# HeaterMeterPI.net
KiCad netlist of a schematic drawn in EAGLE
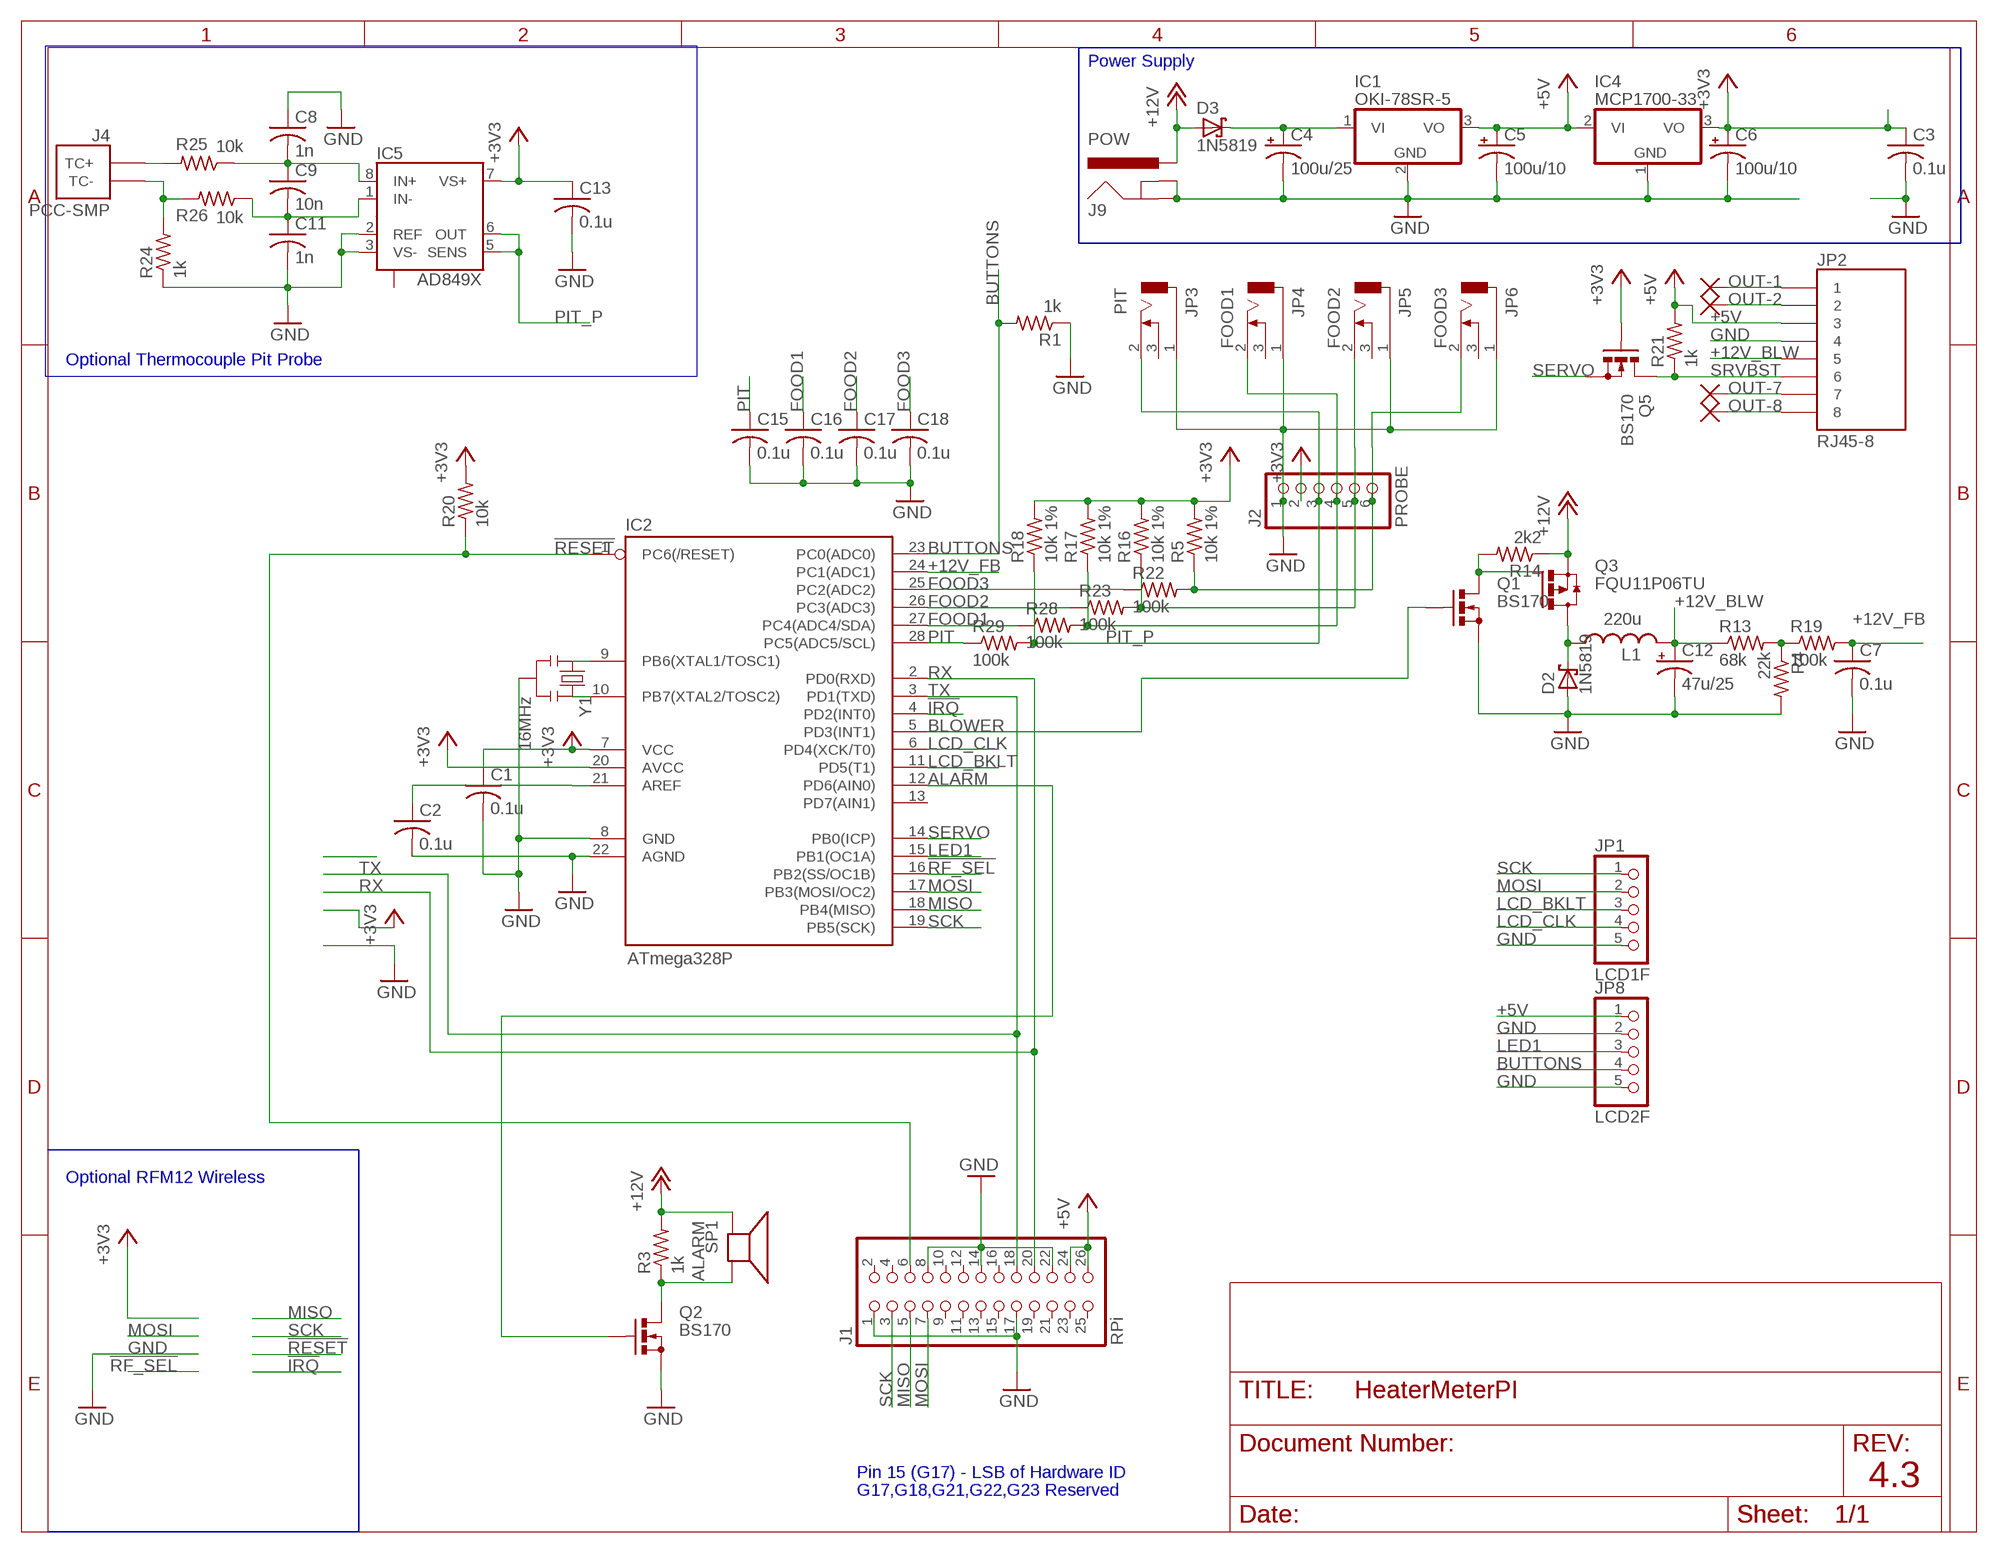
[diagram p0: schematic, sheet 1]

(export (version "E")
  (design (tool "Eeschema 10.0.6"))
  (components
    (comp (ref "C1")
      (value "0.1u")
      (footprint "eagle-import:C025-025X050")
      (libsource (lib "eagle-import") (part "C-US025-025X050"))
    )
    (comp (ref "C2")
      (value "0.1u")
      (footprint "eagle-import:C025-025X050")
      (libsource (lib "eagle-import") (part "C-US025-025X050"))
    )
    (comp (ref "C3")
      (value "0.1u")
      (footprint "eagle-import:C025-025X050")
      (libsource (lib "eagle-import") (part "C-US025-025X050"))
    )
    (comp (ref "C4")
      (value "100u/25")
      (footprint "eagle-import:E2,5-6")
      (libsource (lib "eagle-import") (part "CPOL-USE2.5-6"))
    )
    (comp (ref "C5")
      (value "100u/10")
      (footprint "eagle-import:E2,5-5")
      (libsource (lib "eagle-import") (part "CPOL-USE2.5-5"))
    )
    (comp (ref "C6")
      (value "100u/10")
      (footprint "eagle-import:E2,5-5")
      (libsource (lib "eagle-import") (part "CPOL-USE2.5-5"))
    )
    (comp (ref "C7")
      (value "0.1u")
      (footprint "eagle-import:C025-025X050")
      (libsource (lib "eagle-import") (part "C-US025-025X050"))
    )
    (comp (ref "C8")
      (value "1n")
      (footprint "eagle-import:C0805")
      (libsource (lib "eagle-import") (part "C-USC0805"))
    )
    (comp (ref "C9")
      (value "10n")
      (footprint "eagle-import:C0805")
      (libsource (lib "eagle-import") (part "C-USC0805"))
    )
    (comp (ref "C11")
      (value "1n")
      (footprint "eagle-import:C0805")
      (libsource (lib "eagle-import") (part "C-USC0805"))
    )
    (comp (ref "C12")
      (value "47u/25")
      (footprint "eagle-import:E2,5-5")
      (libsource (lib "eagle-import") (part "CPOL-USE2.5-5"))
    )
    (comp (ref "C13")
      (value "0.1u")
      (footprint "eagle-import:C0805")
      (libsource (lib "eagle-import") (part "C-USC0805"))
    )
    (comp (ref "C15")
      (value "0.1u")
      (footprint "eagle-import:C025-025X050")
      (libsource (lib "eagle-import") (part "C-US025-025X050"))
    )
    (comp (ref "C16")
      (value "0.1u")
      (footprint "eagle-import:C025-025X050")
      (libsource (lib "eagle-import") (part "C-US025-025X050"))
    )
    (comp (ref "C17")
      (value "0.1u")
      (footprint "eagle-import:C025-025X050")
      (libsource (lib "eagle-import") (part "C-US025-025X050"))
    )
    (comp (ref "C18")
      (value "0.1u")
      (footprint "eagle-import:C025-025X050")
      (libsource (lib "eagle-import") (part "C-US025-025X050"))
    )
    (comp (ref "D2")
      (value "1N5819")
      (footprint "eagle-import:DO41-7")
      (libsource (lib "eagle-import") (part "1N5819"))
    )
    (comp (ref "D3")
      (value "1N5819")
      (footprint "eagle-import:DO41-7")
      (libsource (lib "eagle-import") (part "1N5819"))
    )
    (comp (ref "IC1")
      (value "OKI-78SR-5")
      (footprint "eagle-import:TO220HMURATA")
      (libsource (lib "eagle-import") (part "OKI-78SR-H05"))
    )
    (comp (ref "IC2")
      (value "ATmega328P")
      (footprint "eagle-import:DIL28-3")
      (libsource (lib "eagle-import") (part "AVR-MEGA8-PPTH"))
    )
    (comp (ref "IC4")
      (value "MCP1700-33")
      (footprint "eagle-import:TO92")
      (libsource (lib "eagle-import") (part "MCP1700-33"))
    )
    (comp (ref "IC5")
      (value "AD849X")
      (footprint "eagle-import:MSOP8")
      (libsource (lib "eagle-import") (part "AD849X"))
    )
    (comp (ref "J1")
      (value "RPi")
      (footprint "eagle-import:2X13")
      (libsource (lib "eagle-import") (part "PINHD-2X13"))
    )
    (comp (ref "J2")
      (value "PROBE")
      (footprint "eagle-import:1X06")
      (libsource (lib "eagle-import") (part "PINHD-1X6"))
    )
    (comp (ref "J4")
      (value "PCC-SMP")
      (footprint "eagle-import:PCC-SMP")
      (libsource (lib "eagle-import") (part "THERMOCOUPLE"))
    )
    (comp (ref "J9")
      (value "POW")
      (footprint "eagle-import:BARREL-2.1")
      (libsource (lib "eagle-import") (part "POWERJACKPTH"))
    )
    (comp (ref "JP1")
      (value "LCD1F")
      (footprint "eagle-import:1X05")
      (libsource (lib "eagle-import") (part "PINHD-1X5"))
    )
    (comp (ref "JP2")
      (value "RJ45-8")
      (footprint "eagle-import:RJ45-8-1H")
      (libsource (lib "eagle-import") (part "RJ45-8"))
    )
    (comp (ref "JP3")
      (value "PIT")
      (footprint "eagle-import:CUI-MJ-2508")
      (libsource (lib "eagle-import") (part "AUDIO-MONOCUI"))
    )
    (comp (ref "JP4")
      (value "FOOD1")
      (footprint "eagle-import:CUI-MJ-2508")
      (libsource (lib "eagle-import") (part "AUDIO-MONOCUI"))
    )
    (comp (ref "JP5")
      (value "FOOD2")
      (footprint "eagle-import:CUI-MJ-2508")
      (libsource (lib "eagle-import") (part "AUDIO-MONOCUI"))
    )
    (comp (ref "JP6")
      (value "FOOD3")
      (footprint "eagle-import:CUI-MJ-2508")
      (libsource (lib "eagle-import") (part "AUDIO-MONOCUI"))
    )
    (comp (ref "JP8")
      (value "LCD2F")
      (footprint "eagle-import:1X05")
      (libsource (lib "eagle-import") (part "PINHD-1X5"))
    )
    (comp (ref "L1")
      (value "220u")
      (footprint "eagle-import:E5-9")
      (libsource (lib "eagle-import") (part "INDUCTOR9MM"))
    )
    (comp (ref "Q1")
      (value "BS170")
      (footprint "eagle-import:SOT54E")
      (libsource (lib "eagle-import") (part "BS170"))
    )
    (comp (ref "Q2")
      (value "BS170")
      (footprint "eagle-import:SOT54E")
      (libsource (lib "eagle-import") (part "BS170"))
    )
    (comp (ref "Q3")
      (value "FQU11P06TU")
      (footprint "eagle-import:TO251")
      (libsource (lib "eagle-import") (part "MOSFET-P"))
    )
    (comp (ref "Q5")
      (value "BS170")
      (footprint "eagle-import:SOT54E")
      (libsource (lib "eagle-import") (part "BS170"))
    )
    (comp (ref "R1")
      (value "1k")
      (footprint "eagle-import:0204_7")
      (libsource (lib "eagle-import") (part "R-US_0204/7"))
    )
    (comp (ref "R3")
      (value "1k")
      (footprint "eagle-import:0204_7")
      (libsource (lib "eagle-import") (part "R-US_0204/7"))
    )
    (comp (ref "R4")
      (value "22k")
      (footprint "eagle-import:0204_7")
      (libsource (lib "eagle-import") (part "R-US_0204/7"))
    )
    (comp (ref "R5")
      (value "10k 1%")
      (footprint "eagle-import:0207_2V")
      (libsource (lib "eagle-import") (part "R-US_0207/2V"))
    )
    (comp (ref "R13")
      (value "68k")
      (footprint "eagle-import:0204_7")
      (libsource (lib "eagle-import") (part "R-US_0204/7"))
    )
    (comp (ref "R14")
      (value "2k2")
      (footprint "eagle-import:0204_7")
      (libsource (lib "eagle-import") (part "R-US_0204/7"))
    )
    (comp (ref "R16")
      (value "10k 1%")
      (footprint "eagle-import:0207_2V")
      (libsource (lib "eagle-import") (part "R-US_0207/2V"))
    )
    (comp (ref "R17")
      (value "10k 1%")
      (footprint "eagle-import:0207_2V")
      (libsource (lib "eagle-import") (part "R-US_0207/2V"))
    )
    (comp (ref "R18")
      (value "10k 1%")
      (footprint "eagle-import:0207_2V")
      (libsource (lib "eagle-import") (part "R-US_0207/2V"))
    )
    (comp (ref "R19")
      (value "100k")
      (footprint "eagle-import:0204_7")
      (libsource (lib "eagle-import") (part "R-US_0204/7"))
    )
    (comp (ref "R20")
      (value "10k")
      (footprint "eagle-import:0204_7")
      (libsource (lib "eagle-import") (part "R-US_0204/7"))
    )
    (comp (ref "R21")
      (value "1k")
      (footprint "eagle-import:0204_7")
      (libsource (lib "eagle-import") (part "R-US_0204/7"))
    )
    (comp (ref "R22")
      (value "100k")
      (footprint "eagle-import:0207_2V")
      (libsource (lib "eagle-import") (part "R-US_0207/2V"))
    )
    (comp (ref "R23")
      (value "100k")
      (footprint "eagle-import:0207_2V")
      (libsource (lib "eagle-import") (part "R-US_0207/2V"))
    )
    (comp (ref "R24")
      (value "1k")
      (footprint "eagle-import:R0805")
      (libsource (lib "eagle-import") (part "R-US_R0805"))
    )
    (comp (ref "R25")
      (value "10k")
      (footprint "eagle-import:R0805")
      (libsource (lib "eagle-import") (part "R-US_R0805"))
    )
    (comp (ref "R26")
      (value "10k")
      (footprint "eagle-import:R0805")
      (libsource (lib "eagle-import") (part "R-US_R0805"))
    )
    (comp (ref "R28")
      (value "100k")
      (footprint "eagle-import:0207_2V")
      (libsource (lib "eagle-import") (part "R-US_0207/2V"))
    )
    (comp (ref "R29")
      (value "100k")
      (footprint "eagle-import:0207_2V")
      (libsource (lib "eagle-import") (part "R-US_0207/2V"))
    )
    (comp (ref "SP1")
      (value "ALARM")
      (footprint "eagle-import:AL11P")
      (libsource (lib "eagle-import") (part "SPEAKER/AL11P"))
    )
    (comp (ref "U$1")
      (value "THROUGH-HOLE")
      (footprint "eagle-import:PAD-032")
      (libsource (lib "eagle-import") (part "THROUGH-HOLE"))
    )
    (comp (ref "U$2")
      (value "THROUGH-HOLE")
      (footprint "eagle-import:PAD-032")
      (libsource (lib "eagle-import") (part "THROUGH-HOLE"))
    )
    (comp (ref "U$3")
      (value "THROUGH-HOLE")
      (footprint "eagle-import:PAD-032")
      (libsource (lib "eagle-import") (part "THROUGH-HOLE"))
    )
    (comp (ref "U$4")
      (value "THROUGH-HOLE")
      (footprint "eagle-import:PAD-032")
      (libsource (lib "eagle-import") (part "THROUGH-HOLE"))
    )
    (comp (ref "Y1")
      (value "16MHz")
      (footprint "eagle-import:RESONATOR-PTH")
      (libsource (lib "eagle-import") (part "RESONATORRESONATOR-PTH"))
    )
  )
  (nets
    (net (code "1") (name "+3V3") (class "Default")
      (node (ref "C1") (pin "1") (pinfunction "1_1") (pintype "passive"))
      (node (ref "C13") (pin "1") (pinfunction "1_1") (pintype "passive"))
      (node (ref "C3") (pin "1") (pinfunction "1_1") (pintype "passive"))
      (node (ref "C6") (pin "+") (pinfunction "+_+") (pintype "passive"))
      (node (ref "IC2") (pin "20") (pinfunction "AVCC_20") (pintype "bidirectional"))
      (node (ref "IC2") (pin "7") (pinfunction "VCC_7") (pintype "bidirectional"))
      (node (ref "IC4") (pin "3") (pinfunction "VO_3") (pintype "passive"))
      (node (ref "IC5") (pin "7") (pinfunction "VS+_7") (pintype "power_in"))
      (node (ref "J2") (pin "2") (pinfunction "2_2") (pintype "passive"))
      (node (ref "Q5") (pin "G") (pinfunction "G_G") (pintype "passive"))
      (node (ref "R16") (pin "2") (pinfunction "2_2") (pintype "passive"))
      (node (ref "R17") (pin "2") (pinfunction "2_2") (pintype "passive"))
      (node (ref "R18") (pin "2") (pinfunction "2_2") (pintype "passive"))
      (node (ref "R20") (pin "2") (pinfunction "2_2") (pintype "passive"))
      (node (ref "R5") (pin "2") (pinfunction "2_2") (pintype "passive"))
    )
    (net (code "2") (name "+5V") (class "Default")
      (node (ref "C5") (pin "+") (pinfunction "+_+") (pintype "passive"))
      (node (ref "IC1") (pin "3") (pinfunction "VO_3") (pintype "passive"))
      (node (ref "IC4") (pin "2") (pinfunction "VI_2") (pintype "input"))
      (node (ref "J1") (pin "24") (pinfunction "24_24") (pintype "passive"))
      (node (ref "J1") (pin "26") (pinfunction "26_26") (pintype "passive"))
      (node (ref "JP2") (pin "3") (pinfunction "3_3") (pintype "bidirectional"))
      (node (ref "JP8") (pin "1") (pinfunction "1_1") (pintype "passive"))
      (node (ref "R21") (pin "2") (pinfunction "2_2") (pintype "passive"))
    )
    (net (code "3") (name "+12V") (class "Default")
      (node (ref "D3") (pin "A") (pinfunction "A_A") (pintype "passive"))
      (node (ref "J9") (pin "PWR") (pinfunction "PWR_PWR") (pintype "bidirectional"))
      (node (ref "Q3") (pin "3") (pinfunction "S_3") (pintype "passive"))
      (node (ref "R14") (pin "1") (pinfunction "1_1") (pintype "passive"))
      (node (ref "R3") (pin "2") (pinfunction "2_2") (pintype "passive"))
      (node (ref "SP1") (pin "+") (pinfunction "+_+") (pintype "passive"))
    )
    (net (code "4") (name "/+12V_BLW") (class "Default")
      (node (ref "C12") (pin "+") (pinfunction "+_+") (pintype "passive"))
      (node (ref "JP2") (pin "5") (pinfunction "5_5") (pintype "bidirectional"))
      (node (ref "L1") (pin "NEG") (pinfunction "2_NEG") (pintype "passive"))
      (node (ref "R13") (pin "1") (pinfunction "1_1") (pintype "passive"))
    )
    (net (code "5") (name "/+12V_FB") (class "Default")
      (node (ref "C7") (pin "1") (pinfunction "1_1") (pintype "passive"))
      (node (ref "IC2") (pin "24") (pinfunction "PC1(ADC1)_24") (pintype "bidirectional"))
      (node (ref "R19") (pin "2") (pinfunction "2_2") (pintype "passive"))
    )
    (net (code "6") (name "/ALARM") (class "Default")
      (node (ref "IC2") (pin "12") (pinfunction "PD6(AIN0)_12") (pintype "bidirectional"))
      (node (ref "Q2") (pin "G") (pinfunction "G_G") (pintype "passive"))
    )
    (net (code "7") (name "/BLOWER") (class "Default")
      (node (ref "IC2") (pin "5") (pinfunction "PD3(INT1)_5") (pintype "bidirectional"))
      (node (ref "Q1") (pin "G") (pinfunction "G_G") (pintype "passive"))
    )
    (net (code "8") (name "/BUTTONS") (class "Default")
      (node (ref "IC2") (pin "23") (pinfunction "PC0(ADC0)_23") (pintype "bidirectional"))
      (node (ref "JP8") (pin "4") (pinfunction "4_4") (pintype "passive"))
      (node (ref "R1") (pin "2") (pinfunction "2_2") (pintype "passive"))
    )
    (net (code "9") (name "/FOOD1") (class "Default")
      (node (ref "C16") (pin "1") (pinfunction "1_1") (pintype "passive"))
      (node (ref "IC2") (pin "27") (pinfunction "PC4(ADC4/SDA)_27") (pintype "bidirectional"))
      (node (ref "R28") (pin "1") (pinfunction "1_1") (pintype "passive"))
    )
    (net (code "10") (name "/FOOD2") (class "Default")
      (node (ref "C17") (pin "1") (pinfunction "1_1") (pintype "passive"))
      (node (ref "IC2") (pin "26") (pinfunction "PC3(ADC3)_26") (pintype "bidirectional"))
      (node (ref "R23") (pin "1") (pinfunction "1_1") (pintype "passive"))
    )
    (net (code "11") (name "/FOOD3") (class "Default")
      (node (ref "C18") (pin "1") (pinfunction "1_1") (pintype "passive"))
      (node (ref "IC2") (pin "25") (pinfunction "PC2(ADC2)_25") (pintype "bidirectional"))
      (node (ref "R22") (pin "1") (pinfunction "1_1") (pintype "passive"))
    )
    (net (code "12") (name "/LCD_BKLT") (class "Default")
      (node (ref "IC2") (pin "11") (pinfunction "PD5(T1)_11") (pintype "bidirectional"))
      (node (ref "JP1") (pin "3") (pinfunction "3_3") (pintype "passive"))
    )
    (net (code "13") (name "/LCD_CLK") (class "Default")
      (node (ref "IC2") (pin "6") (pinfunction "PD4(XCK/T0)_6") (pintype "bidirectional"))
      (node (ref "JP1") (pin "4") (pinfunction "4_4") (pintype "passive"))
    )
    (net (code "14") (name "/LED1") (class "Default")
      (node (ref "IC2") (pin "15") (pinfunction "PB1(OC1A)_15") (pintype "bidirectional"))
      (node (ref "JP8") (pin "3") (pinfunction "3_3") (pintype "passive"))
    )
    (net (code "15") (name "/MISO") (class "Default")
      (node (ref "IC2") (pin "18") (pinfunction "PB4(MISO)_18") (pintype "bidirectional"))
      (node (ref "J1") (pin "5") (pinfunction "5_5") (pintype "passive"))
    )
    (net (code "16") (name "/MOSI") (class "Default")
      (node (ref "IC2") (pin "17") (pinfunction "PB3(MOSI/OC2)_17") (pintype "bidirectional"))
      (node (ref "J1") (pin "7") (pinfunction "7_7") (pintype "passive"))
      (node (ref "JP1") (pin "2") (pinfunction "2_2") (pintype "passive"))
    )
    (net (code "17") (name "/OUT-1") (class "Default")
      (node (ref "JP2") (pin "1") (pinfunction "1_1") (pintype "bidirectional"))
      (node (ref "U$3") (pin "P") (pinfunction "P_P") (pintype "output"))
    )
    (net (code "18") (name "/OUT-2") (class "Default")
      (node (ref "JP2") (pin "2") (pinfunction "2_2") (pintype "bidirectional"))
      (node (ref "U$4") (pin "P") (pinfunction "P_P") (pintype "output"))
    )
    (net (code "19") (name "/OUT-7") (class "Default")
      (node (ref "JP2") (pin "7") (pinfunction "7_7") (pintype "bidirectional"))
      (node (ref "U$2") (pin "P") (pinfunction "P_P") (pintype "output"))
    )
    (net (code "20") (name "/OUT-8") (class "Default")
      (node (ref "JP2") (pin "8") (pinfunction "8_8") (pintype "bidirectional"))
      (node (ref "U$1") (pin "P") (pinfunction "P_P") (pintype "output"))
    )
    (net (code "21") (name "/PIT") (class "Default")
      (node (ref "C15") (pin "1") (pinfunction "1_1") (pintype "passive"))
      (node (ref "IC2") (pin "28") (pinfunction "PC5(ADC5/SCL)_28") (pintype "bidirectional"))
      (node (ref "R29") (pin "1") (pinfunction "1_1") (pintype "passive"))
    )
    (net (code "22") (name "/PIT_P") (class "Default")
      (node (ref "IC5") (pin "5") (pinfunction "SENS_5") (pintype "bidirectional"))
      (node (ref "IC5") (pin "6") (pinfunction "OUT_6") (pintype "output"))
      (node (ref "J2") (pin "3") (pinfunction "3_3") (pintype "passive"))
      (node (ref "JP3") (pin "2") (pinfunction "2_2") (pintype "passive"))
      (node (ref "R18") (pin "1") (pinfunction "1_1") (pintype "passive"))
      (node (ref "R29") (pin "2") (pinfunction "2_2") (pintype "passive"))
    )
    (net (code "23") (name "/RX") (class "Default")
      (node (ref "IC2") (pin "2") (pinfunction "PD0(RXD)_2") (pintype "bidirectional"))
      (node (ref "J1") (pin "20") (pinfunction "20_20") (pintype "passive"))
    )
    (net (code "24") (name "/SCK") (class "Default")
      (node (ref "IC2") (pin "19") (pinfunction "PB5(SCK)_19") (pintype "bidirectional"))
      (node (ref "J1") (pin "3") (pinfunction "3_3") (pintype "passive"))
      (node (ref "JP1") (pin "1") (pinfunction "1_1") (pintype "passive"))
    )
    (net (code "25") (name "/SERVO") (class "Default")
      (node (ref "IC2") (pin "14") (pinfunction "PB0(ICP)_14") (pintype "bidirectional"))
      (node (ref "Q5") (pin "S") (pinfunction "S_S") (pintype "passive"))
    )
    (net (code "26") (name "/SRVBST") (class "Default")
      (node (ref "JP2") (pin "6") (pinfunction "6_6") (pintype "bidirectional"))
      (node (ref "Q5") (pin "D") (pinfunction "D_D") (pintype "passive"))
      (node (ref "R21") (pin "1") (pinfunction "1_1") (pintype "passive"))
    )
    (net (code "27") (name "/TX") (class "Default")
      (node (ref "IC2") (pin "3") (pinfunction "PD1(TXD)_3") (pintype "bidirectional"))
      (node (ref "J1") (pin "18") (pinfunction "18_18") (pintype "passive"))
    )
    (net (code "28") (name "/~{IRQ}") (class "Default")
      (node (ref "IC2") (pin "4") (pinfunction "PD2(INT0)_4") (pintype "bidirectional"))
    )
    (net (code "29") (name "/~{RESET}") (class "Default")
      (node (ref "IC2") (pin "1") (pinfunction "PC6(/RESET)_1") (pintype "bidirectional"))
      (node (ref "J1") (pin "6") (pinfunction "6_6") (pintype "passive"))
      (node (ref "R20") (pin "1") (pinfunction "1_1") (pintype "passive"))
    )
    (net (code "30") (name "/~{RF_SEL}") (class "Default")
      (node (ref "IC2") (pin "16") (pinfunction "PB2(SS/OC1B)_16") (pintype "bidirectional"))
    )
    (net (code "31") (name "GND") (class "Default")
      (node (ref "C1") (pin "2") (pinfunction "2_2") (pintype "passive"))
      (node (ref "C11") (pin "2") (pinfunction "2_2") (pintype "passive"))
      (node (ref "C12") (pin "-") (pinfunction "-_-") (pintype "passive"))
      (node (ref "C13") (pin "2") (pinfunction "2_2") (pintype "passive"))
      (node (ref "C15") (pin "2") (pinfunction "2_2") (pintype "passive"))
      (node (ref "C16") (pin "2") (pinfunction "2_2") (pintype "passive"))
      (node (ref "C17") (pin "2") (pinfunction "2_2") (pintype "passive"))
      (node (ref "C18") (pin "2") (pinfunction "2_2") (pintype "passive"))
      (node (ref "C2") (pin "2") (pinfunction "2_2") (pintype "passive"))
      (node (ref "C3") (pin "2") (pinfunction "2_2") (pintype "passive"))
      (node (ref "C4") (pin "-") (pinfunction "-_-") (pintype "passive"))
      (node (ref "C5") (pin "-") (pinfunction "-_-") (pintype "passive"))
      (node (ref "C6") (pin "-") (pinfunction "-_-") (pintype "passive"))
      (node (ref "C7") (pin "2") (pinfunction "2_2") (pintype "passive"))
      (node (ref "C8") (pin "1") (pinfunction "1_1") (pintype "passive"))
      (node (ref "D2") (pin "A") (pinfunction "A_A") (pintype "passive"))
      (node (ref "IC1") (pin "2") (pinfunction "GND_2") (pintype "passive"))
      (node (ref "IC2") (pin "22") (pinfunction "AGND_22") (pintype "bidirectional"))
      (node (ref "IC2") (pin "8") (pinfunction "GND_8") (pintype "bidirectional"))
      (node (ref "IC4") (pin "1") (pinfunction "GND_1") (pintype "passive"))
      (node (ref "IC5") (pin "2") (pinfunction "REF_2") (pintype "input"))
      (node (ref "IC5") (pin "3") (pinfunction "VS-_3") (pintype "power_in"))
      (node (ref "J1") (pin "1") (pinfunction "1_1") (pintype "passive"))
      (node (ref "J1") (pin "14") (pinfunction "14_14") (pintype "passive"))
      (node (ref "J1") (pin "17") (pinfunction "17_17") (pintype "passive"))
      (node (ref "J1") (pin "22") (pinfunction "22_22") (pintype "passive"))
      (node (ref "J1") (pin "8") (pinfunction "8_8") (pintype "passive"))
      (node (ref "J2") (pin "1") (pinfunction "1_1") (pintype "passive"))
      (node (ref "J9") (pin "GND") (pinfunction "GND_GND") (pintype "bidirectional"))
      (node (ref "J9") (pin "GNDBREAK") (pinfunction "GNDBREAK_GNDBREAK") (pintype "bidirectional"))
      (node (ref "JP1") (pin "5") (pinfunction "5_5") (pintype "passive"))
      (node (ref "JP2") (pin "4") (pinfunction "4_4") (pintype "bidirectional"))
      (node (ref "JP3") (pin "1") (pinfunction "1_1") (pintype "passive"))
      (node (ref "JP4") (pin "1") (pinfunction "1_1") (pintype "passive"))
      (node (ref "JP5") (pin "1") (pinfunction "1_1") (pintype "passive"))
      (node (ref "JP6") (pin "1") (pinfunction "1_1") (pintype "passive"))
      (node (ref "JP8") (pin "2") (pinfunction "2_2") (pintype "passive"))
      (node (ref "JP8") (pin "5") (pinfunction "5_5") (pintype "passive"))
      (node (ref "Q1") (pin "S") (pinfunction "S_S") (pintype "passive"))
      (node (ref "Q2") (pin "S") (pinfunction "S_S") (pintype "passive"))
      (node (ref "R1") (pin "1") (pinfunction "1_1") (pintype "passive"))
      (node (ref "R24") (pin "1") (pinfunction "1_1") (pintype "passive"))
      (node (ref "R4") (pin "2") (pinfunction "2_2") (pintype "passive"))
      (node (ref "Y1") (pin "2") (pinfunction "2_2") (pintype "passive"))
    )
    (net (code "32") (name "Net-(IC1-VI)") (class "Default")
      (node (ref "C4") (pin "+") (pinfunction "+_+") (pintype "passive"))
      (node (ref "D3") (pin "C") (pinfunction "C_C") (pintype "passive"))
      (node (ref "IC1") (pin "1") (pinfunction "VI_1") (pintype "input"))
    )
    (net (code "33") (name "Net-(IC2-AREF)") (class "Default")
      (node (ref "C2") (pin "1") (pinfunction "1_1") (pintype "passive"))
      (node (ref "IC2") (pin "21") (pinfunction "AREF_21") (pintype "bidirectional"))
    )
    (net (code "34") (name "Net-(IC2-PB6(XTAL1{slash}TOSC1))") (class "Default")
      (node (ref "IC2") (pin "9") (pinfunction "PB6(XTAL1/TOSC1)_9") (pintype "bidirectional"))
      (node (ref "Y1") (pin "1") (pinfunction "1_1") (pintype "passive"))
    )
    (net (code "35") (name "Net-(IC2-PB7(XTAL2{slash}TOSC2))") (class "Default")
      (node (ref "IC2") (pin "10") (pinfunction "PB7(XTAL2/TOSC2)_10") (pintype "bidirectional"))
      (node (ref "Y1") (pin "3") (pinfunction "3_3") (pintype "passive"))
    )
    (net (code "36") (name "Net-(IC5-IN+)") (class "Default")
      (node (ref "C8") (pin "2") (pinfunction "2_2") (pintype "passive"))
      (node (ref "C9") (pin "1") (pinfunction "1_1") (pintype "passive"))
      (node (ref "IC5") (pin "8") (pinfunction "IN+_8") (pintype "input"))
      (node (ref "R25") (pin "1") (pinfunction "1_1") (pintype "passive"))
    )
    (net (code "37") (name "Net-(IC5-IN-)") (class "Default")
      (node (ref "C11") (pin "1") (pinfunction "1_1") (pintype "passive"))
      (node (ref "C9") (pin "2") (pinfunction "2_2") (pintype "passive"))
      (node (ref "IC5") (pin "1") (pinfunction "IN-_1") (pintype "input"))
      (node (ref "R26") (pin "1") (pinfunction "1_1") (pintype "passive"))
    )
    (net (code "38") (name "Net-(J2-Pad4)") (class "Default")
      (node (ref "J2") (pin "4") (pinfunction "4_4") (pintype "passive"))
      (node (ref "JP4") (pin "2") (pinfunction "2_2") (pintype "passive"))
      (node (ref "R17") (pin "1") (pinfunction "1_1") (pintype "passive"))
      (node (ref "R28") (pin "2") (pinfunction "2_2") (pintype "passive"))
    )
    (net (code "39") (name "Net-(J2-Pad5)") (class "Default")
      (node (ref "J2") (pin "5") (pinfunction "5_5") (pintype "passive"))
      (node (ref "JP5") (pin "2") (pinfunction "2_2") (pintype "passive"))
      (node (ref "R16") (pin "1") (pinfunction "1_1") (pintype "passive"))
      (node (ref "R23") (pin "2") (pinfunction "2_2") (pintype "passive"))
    )
    (net (code "40") (name "Net-(J2-Pad6)") (class "Default")
      (node (ref "J2") (pin "6") (pinfunction "6_6") (pintype "passive"))
      (node (ref "JP6") (pin "2") (pinfunction "2_2") (pintype "passive"))
      (node (ref "R22") (pin "2") (pinfunction "2_2") (pintype "passive"))
      (node (ref "R5") (pin "1") (pinfunction "1_1") (pintype "passive"))
    )
    (net (code "41") (name "Net-(J4-PadTC+)") (class "Default")
      (node (ref "J4") (pin "TC+") (pinfunction "TC+_TC+") (pintype "bidirectional"))
      (node (ref "R25") (pin "2") (pinfunction "2_2") (pintype "passive"))
    )
    (net (code "42") (name "Net-(J4-PadTC-)") (class "Default")
      (node (ref "J4") (pin "TC-") (pinfunction "TC-_TC-") (pintype "bidirectional"))
      (node (ref "R24") (pin "2") (pinfunction "2_2") (pintype "passive"))
      (node (ref "R26") (pin "2") (pinfunction "2_2") (pintype "passive"))
    )
    (net (code "43") (name "Net-(L1-1)") (class "Default")
      (node (ref "D2") (pin "C") (pinfunction "C_C") (pintype "passive"))
      (node (ref "L1") (pin "POS") (pinfunction "1_POS") (pintype "passive"))
      (node (ref "Q3") (pin "2@1") (pinfunction "D_2@1") (pintype "passive"))
      (node (ref "Q3") (pin "2@2") (pinfunction "D_2@2") (pintype "passive"))
    )
    (net (code "44") (name "Net-(Q2-PadD)") (class "Default")
      (node (ref "Q2") (pin "D") (pinfunction "D_D") (pintype "passive"))
      (node (ref "R3") (pin "1") (pinfunction "1_1") (pintype "passive"))
      (node (ref "SP1") (pin "-") (pinfunction "-_-") (pintype "passive"))
    )
    (net (code "45") (name "Net-(Q3-G)") (class "Default")
      (node (ref "Q1") (pin "D") (pinfunction "D_D") (pintype "passive"))
      (node (ref "Q3") (pin "1") (pinfunction "G_1") (pintype "passive"))
      (node (ref "R14") (pin "2") (pinfunction "2_2") (pintype "passive"))
    )
    (net (code "46") (name "Net-(R13-Pad2)") (class "Default")
      (node (ref "R13") (pin "2") (pinfunction "2_2") (pintype "passive"))
      (node (ref "R19") (pin "1") (pinfunction "1_1") (pintype "passive"))
      (node (ref "R4") (pin "1") (pinfunction "1_1") (pintype "passive"))
    )
    (net (code "47") (name "unconnected-(IC2-PD7(AIN1)-Pad13)") (class "Default")
      (node (ref "IC2") (pin "13") (pinfunction "PD7(AIN1)_13") (pintype "bidirectional"))
    )
    (net (code "48") (name "unconnected-(IC5-NC-Pad4)") (class "Default")
      (node (ref "IC5") (pin "4") (pinfunction "NC_4") (pintype "no_connect"))
    )
    (net (code "49") (name "unconnected-(J1-Pad2)") (class "Default")
      (node (ref "J1") (pin "2") (pinfunction "2_2") (pintype "passive"))
    )
    (net (code "50") (name "unconnected-(J1-Pad4)") (class "Default")
      (node (ref "J1") (pin "4") (pinfunction "4_4") (pintype "passive"))
    )
    (net (code "51") (name "unconnected-(J1-Pad9)") (class "Default")
      (node (ref "J1") (pin "9") (pinfunction "9_9") (pintype "passive"))
    )
    (net (code "52") (name "unconnected-(J1-Pad10)") (class "Default")
      (node (ref "J1") (pin "10") (pinfunction "10_10") (pintype "passive"))
    )
    (net (code "53") (name "unconnected-(J1-Pad11)") (class "Default")
      (node (ref "J1") (pin "11") (pinfunction "11_11") (pintype "passive"))
    )
    (net (code "54") (name "unconnected-(J1-Pad12)") (class "Default")
      (node (ref "J1") (pin "12") (pinfunction "12_12") (pintype "passive"))
    )
    (net (code "55") (name "unconnected-(J1-Pad13)") (class "Default")
      (node (ref "J1") (pin "13") (pinfunction "13_13") (pintype "passive"))
    )
    (net (code "56") (name "unconnected-(J1-Pad15)") (class "Default")
      (node (ref "J1") (pin "15") (pinfunction "15_15") (pintype "passive"))
    )
    (net (code "57") (name "unconnected-(J1-Pad16)") (class "Default")
      (node (ref "J1") (pin "16") (pinfunction "16_16") (pintype "passive"))
    )
    (net (code "58") (name "unconnected-(J1-Pad19)") (class "Default")
      (node (ref "J1") (pin "19") (pinfunction "19_19") (pintype "passive"))
    )
    (net (code "59") (name "unconnected-(J1-Pad21)") (class "Default")
      (node (ref "J1") (pin "21") (pinfunction "21_21") (pintype "passive"))
    )
    (net (code "60") (name "unconnected-(J1-Pad23)") (class "Default")
      (node (ref "J1") (pin "23") (pinfunction "23_23") (pintype "passive"))
    )
    (net (code "61") (name "unconnected-(J1-Pad25)") (class "Default")
      (node (ref "J1") (pin "25") (pinfunction "25_25") (pintype "passive"))
    )
    (net (code "62") (name "unconnected-(JP3-Pad3)") (class "Default")
      (node (ref "JP3") (pin "3") (pinfunction "3_3") (pintype "passive"))
    )
    (net (code "63") (name "unconnected-(JP4-Pad3)") (class "Default")
      (node (ref "JP4") (pin "3") (pinfunction "3_3") (pintype "passive"))
    )
    (net (code "64") (name "unconnected-(JP5-Pad3)") (class "Default")
      (node (ref "JP5") (pin "3") (pinfunction "3_3") (pintype "passive"))
    )
    (net (code "65") (name "unconnected-(JP6-Pad3)") (class "Default")
      (node (ref "JP6") (pin "3") (pinfunction "3_3") (pintype "passive"))
    )
  )
)
